# Battery_Charger.net
KiCad netlist of a schematic drawn in Altium Designer
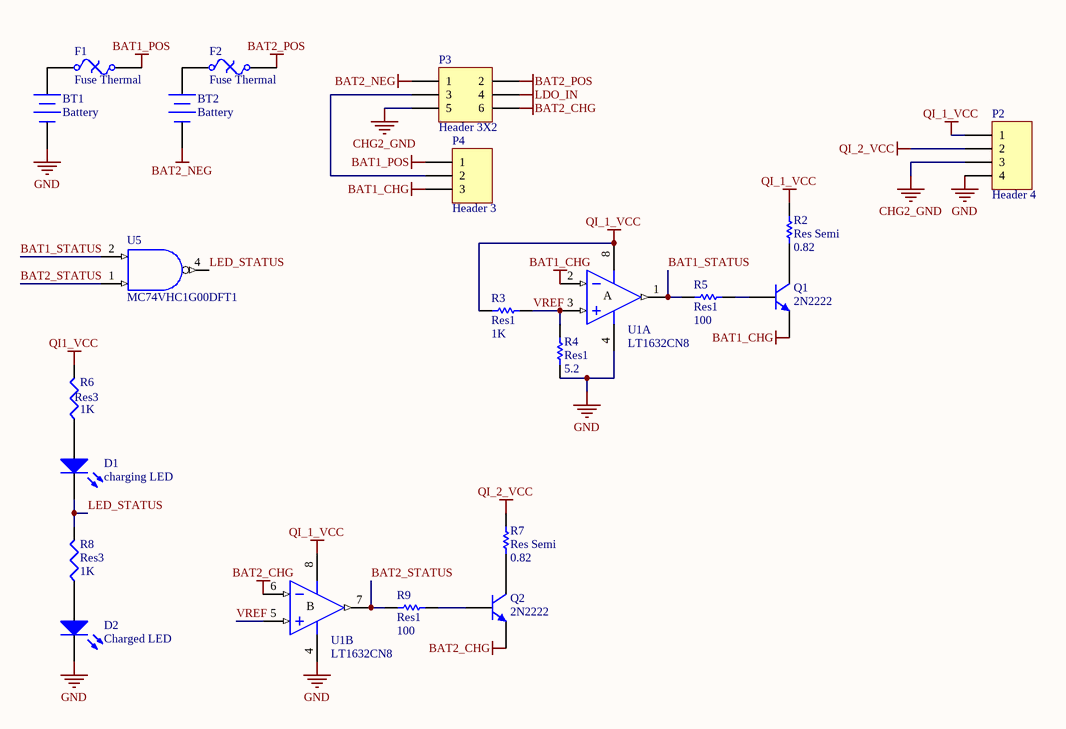
[diagram p0: Battery Charger.SchDoc]

(export (version "E")
  (design (tool "Eeschema 10.0.6"))
  (components
    (comp (ref "BT1")
      (value "Battery")
      (footprint "BAT-2")
      (description "Multicell Battery")
      (fields (field (name "PUBLISHER") "Altium Limited"))
      (libsource (lib "Miscellaneous Devices") (part "Battery"))
    )
    (comp (ref "BT2")
      (value "Battery")
      (footprint "BAT-2")
      (description "Multicell Battery")
      (fields (field (name "PUBLISHER") "Altium Limited"))
      (libsource (lib "Miscellaneous Devices") (part "Battery"))
    )
    (comp (ref "D1")
      (value "charging LED")
      (footprint "LED-0")
      (description "Typical INFRARED GaAs LED")
      (fields (field (name "PUBLISHER") "Altium Limited"))
      (libsource (lib "Miscellaneous Devices") (part "LED0"))
    )
    (comp (ref "D2")
      (value "Charged LED")
      (footprint "LED-0")
      (description "Typical INFRARED GaAs LED")
      (fields (field (name "PUBLISHER") "Altium Limited"))
      (libsource (lib "Miscellaneous Devices") (part "LED0"))
    )
    (comp (ref "F1")
      (value "Fuse Thermal")
      (footprint "PIN-W2/E2.8")
      (description "Thermal Fuse")
      (fields (field (name "PUBLISHER") "Altium Limited"))
      (libsource (lib "Miscellaneous Devices") (part "Fuse Thermal"))
    )
    (comp (ref "F2")
      (value "Fuse Thermal")
      (footprint "PIN-W2/E2.8")
      (description "Thermal Fuse")
      (fields (field (name "PUBLISHER") "Altium Limited"))
      (libsource (lib "Miscellaneous Devices") (part "Fuse Thermal"))
    )
    (comp (ref "P2")
      (value "Header 4")
      (footprint "HDR1X4")
      (description "Header, 4-Pin")
      (fields (field (name "PUBLISHER") "Altium Limited"))
      (libsource (lib "Miscellaneous Connectors") (part "Header 4"))
    )
    (comp (ref "P3")
      (value "Header 3X2")
      (footprint "HDR2X3")
      (description "Header, 3-Pin, Dual row")
      (fields (field (name "PUBLISHER") "Altium Limited"))
      (libsource (lib "Miscellaneous Connectors") (part "Header 3X2"))
    )
    (comp (ref "P4")
      (value "Header 3")
      (footprint "HDR1X3")
      (description "Header, 3-Pin")
      (fields (field (name "PUBLISHER") "Altium Limited"))
      (libsource (lib "Miscellaneous Connectors") (part "Header 3"))
    )
    (comp (ref "Q1")
      (value "2N2222")
      (footprint "TO-92A")
      (description "NPN General Purpose Amplifier")
      (fields (field (name "PUBLISHER") "Altium Limited"))
      (libsource (lib "Miscellaneous Devices") (part "2N3904"))
    )
    (comp (ref "Q2")
      (value "2N2222")
      (footprint "TO-92A")
      (description "NPN General Purpose Amplifier")
      (fields (field (name "PUBLISHER") "Altium Limited"))
      (libsource (lib "Miscellaneous Devices") (part "2N3904"))
    )
    (comp (ref "R2")
      (value "Res Semi")
      (footprint "AXIAL-0.5")
      (description "Semiconductor Resistor")
      (fields (field (name "ALTIUM_VALUE") "0.82") (field (name "PUBLISHER") "Altium Limited"))
      (libsource (lib "Miscellaneous Devices") (part "Res Semi"))
    )
    (comp (ref "R3")
      (value "Res1")
      (footprint "AXIAL-0.3")
      (description "Resistor")
      (fields (field (name "ALTIUM_VALUE") "1K") (field (name "PUBLISHER") "Altium Limited"))
      (libsource (lib "Miscellaneous Devices") (part "Res1"))
    )
    (comp (ref "R4")
      (value "Res1")
      (footprint "AXIAL-0.3")
      (description "Resistor")
      (fields (field (name "ALTIUM_VALUE") "5.2") (field (name "PUBLISHER") "Altium Limited"))
      (libsource (lib "Miscellaneous Devices") (part "Res1"))
    )
    (comp (ref "R5")
      (value "Res1")
      (footprint "AXIAL-0.3")
      (description "Resistor")
      (fields (field (name "ALTIUM_VALUE") "100") (field (name "PUBLISHER") "Altium Limited"))
      (libsource (lib "Miscellaneous Devices") (part "Res1"))
    )
    (comp (ref "R6")
      (value "Res3")
      (footprint "14-1210")
      (description "Resistor")
      (fields (field (name "ALTIUM_VALUE") "1K") (field (name "PUBLISHER") "Altium Limited"))
      (libsource (lib "Miscellaneous Devices") (part "Res3"))
    )
    (comp (ref "R7")
      (value "Res Semi")
      (footprint "AXIAL-0.5")
      (description "Semiconductor Resistor")
      (fields (field (name "ALTIUM_VALUE") "0.82") (field (name "PUBLISHER") "Altium Limited"))
      (libsource (lib "Miscellaneous Devices") (part "Res Semi"))
    )
    (comp (ref "R8")
      (value "Res3")
      (footprint "14-1210")
      (description "Resistor")
      (fields (field (name "ALTIUM_VALUE") "1K") (field (name "PUBLISHER") "Altium Limited"))
      (libsource (lib "Miscellaneous Devices") (part "Res3"))
    )
    (comp (ref "R9")
      (value "Res1")
      (footprint "AXIAL-0.3")
      (description "Resistor")
      (fields (field (name "ALTIUM_VALUE") "100") (field (name "PUBLISHER") "Altium Limited"))
      (libsource (lib "Miscellaneous Devices") (part "Res1"))
    )
    (comp (ref "U1")
      (value "LT1632CN8")
      (footprint "DIP-8")
      (description "45MHz, 45V/µs, Dual Rail-to-Rail Input and Output Precision Operational Amplifier")
      (fields (field (name "PUBLISHER") "Altium Limited"))
      (libsource (lib "ECE LIB new") (part "LT1632CN8"))
    )
    (comp (ref "U5")
      (value "MC74VHC1G00DFT1")
      (footprint "419A-01_N")
      (description "2-Input NAND Gate")
      (fields (field (name "PUBLISHER") "Altium Limited"))
      (libsource (lib "ON Semi Logic Gate") (part "MC74VHC1G00DFT1"))
    )
  )
  (nets
    (net (code "1") (name "/BAT1_STATUS") (class "Default")
      (node (ref "R5") (pin "1") (pinfunction "1_1") (pintype "passive"))
      (node (ref "U1") (pin "1") (pinfunction "OUT_1") (pintype "output"))
      (node (ref "U5") (pin "2") (pinfunction "A_2") (pintype "input"))
    )
    (net (code "2") (name "/BAT2_STATUS") (class "Default")
      (node (ref "R9") (pin "1") (pinfunction "1_1") (pintype "passive"))
      (node (ref "U1") (pin "7") (pinfunction "OUT_7") (pintype "output"))
      (node (ref "U5") (pin "1") (pinfunction "B_1") (pintype "input"))
    )
    (net (code "3") (name "/LED_STATUS") (class "Default")
      (node (ref "D1") (pin "2") (pinfunction "K_2") (pintype "passive"))
      (node (ref "R8") (pin "2") (pinfunction "2_2") (pintype "passive"))
      (node (ref "U5") (pin "4") (pinfunction "~{Y}_4") (pintype "output"))
    )
    (net (code "4") (name "/VREF") (class "Default")
      (node (ref "R3") (pin "2") (pinfunction "2_2") (pintype "passive"))
      (node (ref "R4") (pin "2") (pinfunction "2_2") (pintype "passive"))
      (node (ref "U1") (pin "3") (pinfunction "IN+_3") (pintype "input"))
      (node (ref "U1") (pin "5") (pinfunction "IN+_5") (pintype "input"))
    )
    (net (code "5") (name "BAT1_CHG") (class "Default")
      (node (ref "P4") (pin "3") (pinfunction "3_3") (pintype "passive"))
      (node (ref "Q1") (pin "1") (pinfunction "E_1") (pintype "passive"))
      (node (ref "U1") (pin "2") (pinfunction "IN-_2") (pintype "input"))
    )
    (net (code "6") (name "BAT1_POS") (class "Default")
      (node (ref "F1") (pin "1") (pinfunction "1_1") (pintype "passive"))
      (node (ref "P4") (pin "1") (pinfunction "1_1") (pintype "passive"))
    )
    (net (code "7") (name "BAT2_CHG") (class "Default")
      (node (ref "P3") (pin "6") (pinfunction "6_6") (pintype "passive"))
      (node (ref "Q2") (pin "1") (pinfunction "E_1") (pintype "passive"))
      (node (ref "U1") (pin "6") (pinfunction "IN-_6") (pintype "input"))
    )
    (net (code "8") (name "BAT2_NEG") (class "Default")
      (node (ref "BT2") (pin "2") (pinfunction "-_2") (pintype "passive"))
      (node (ref "P3") (pin "1") (pinfunction "1_1") (pintype "passive"))
    )
    (net (code "9") (name "BAT2_POS") (class "Default")
      (node (ref "F2") (pin "1") (pinfunction "1_1") (pintype "passive"))
      (node (ref "P3") (pin "2") (pinfunction "2_2") (pintype "passive"))
    )
    (net (code "10") (name "CHG2_GND") (class "Default")
      (node (ref "P2") (pin "3") (pinfunction "3_3") (pintype "passive"))
      (node (ref "P3") (pin "5") (pinfunction "5_5") (pintype "passive"))
    )
    (net (code "11") (name "GND") (class "Default")
      (node (ref "BT1") (pin "2") (pinfunction "-_2") (pintype "passive"))
      (node (ref "D2") (pin "2") (pinfunction "K_2") (pintype "passive"))
      (node (ref "P2") (pin "4") (pinfunction "4_4") (pintype "passive"))
      (node (ref "R4") (pin "1") (pinfunction "1_1") (pintype "passive"))
      (node (ref "U1") (pin "4") (pinfunction "V-_4") (pintype "power_in"))
      (node (ref "U5") (pin "3") (pinfunction "GND_3") (pintype "power_in"))
    )
    (net (code "12") (name "LDO_IN") (class "Default")
      (node (ref "P3") (pin "4") (pinfunction "4_4") (pintype "passive"))
    )
    (net (code "13") (name "Net-(BT1-+)") (class "Default")
      (node (ref "BT1") (pin "1") (pinfunction "+_1") (pintype "passive"))
      (node (ref "F1") (pin "2") (pinfunction "2_2") (pintype "passive"))
    )
    (net (code "14") (name "Net-(BT2-+)") (class "Default")
      (node (ref "BT2") (pin "1") (pinfunction "+_1") (pintype "passive"))
      (node (ref "F2") (pin "2") (pinfunction "2_2") (pintype "passive"))
    )
    (net (code "15") (name "Net-(D1-A)") (class "Default")
      (node (ref "D1") (pin "1") (pinfunction "A_1") (pintype "passive"))
      (node (ref "R6") (pin "1") (pinfunction "1_1") (pintype "passive"))
    )
    (net (code "16") (name "Net-(D2-A)") (class "Default")
      (node (ref "D2") (pin "1") (pinfunction "A_1") (pintype "passive"))
      (node (ref "R8") (pin "1") (pinfunction "1_1") (pintype "passive"))
    )
    (net (code "17") (name "Net-(P3-Pad3)") (class "Default")
      (node (ref "P3") (pin "3") (pinfunction "3_3") (pintype "passive"))
      (node (ref "P4") (pin "2") (pinfunction "2_2") (pintype "passive"))
    )
    (net (code "18") (name "Net-(Q1-B)") (class "Default")
      (node (ref "Q1") (pin "2") (pinfunction "B_2") (pintype "passive"))
      (node (ref "R5") (pin "2") (pinfunction "2_2") (pintype "passive"))
    )
    (net (code "19") (name "Net-(Q1-C)") (class "Default")
      (node (ref "Q1") (pin "3") (pinfunction "C_3") (pintype "passive"))
      (node (ref "R2") (pin "1") (pinfunction "1_1") (pintype "passive"))
    )
    (net (code "20") (name "Net-(Q2-B)") (class "Default")
      (node (ref "Q2") (pin "2") (pinfunction "B_2") (pintype "passive"))
      (node (ref "R9") (pin "2") (pinfunction "2_2") (pintype "passive"))
    )
    (net (code "21") (name "Net-(Q2-C)") (class "Default")
      (node (ref "Q2") (pin "3") (pinfunction "C_3") (pintype "passive"))
      (node (ref "R7") (pin "1") (pinfunction "1_1") (pintype "passive"))
    )
    (net (code "22") (name "QI1_VCC") (class "Default")
      (node (ref "R6") (pin "2") (pinfunction "2_2") (pintype "passive"))
    )
    (net (code "23") (name "QI_1_VCC") (class "Default")
      (node (ref "P2") (pin "1") (pinfunction "1_1") (pintype "passive"))
      (node (ref "R2") (pin "2") (pinfunction "2_2") (pintype "passive"))
      (node (ref "R3") (pin "1") (pinfunction "1_1") (pintype "passive"))
      (node (ref "U1") (pin "8") (pinfunction "V+_8") (pintype "power_in"))
    )
    (net (code "24") (name "QI_2_VCC") (class "Default")
      (node (ref "P2") (pin "2") (pinfunction "2_2") (pintype "passive"))
      (node (ref "R7") (pin "2") (pinfunction "2_2") (pintype "passive"))
    )
    (net (code "25") (name "VDD") (class "Default")
      (node (ref "U5") (pin "5") (pinfunction "VDD_5") (pintype "power_in"))
    )
  )
)
